# config-ground.net
KiCad netlist of a schematic drawn in Altium Designer
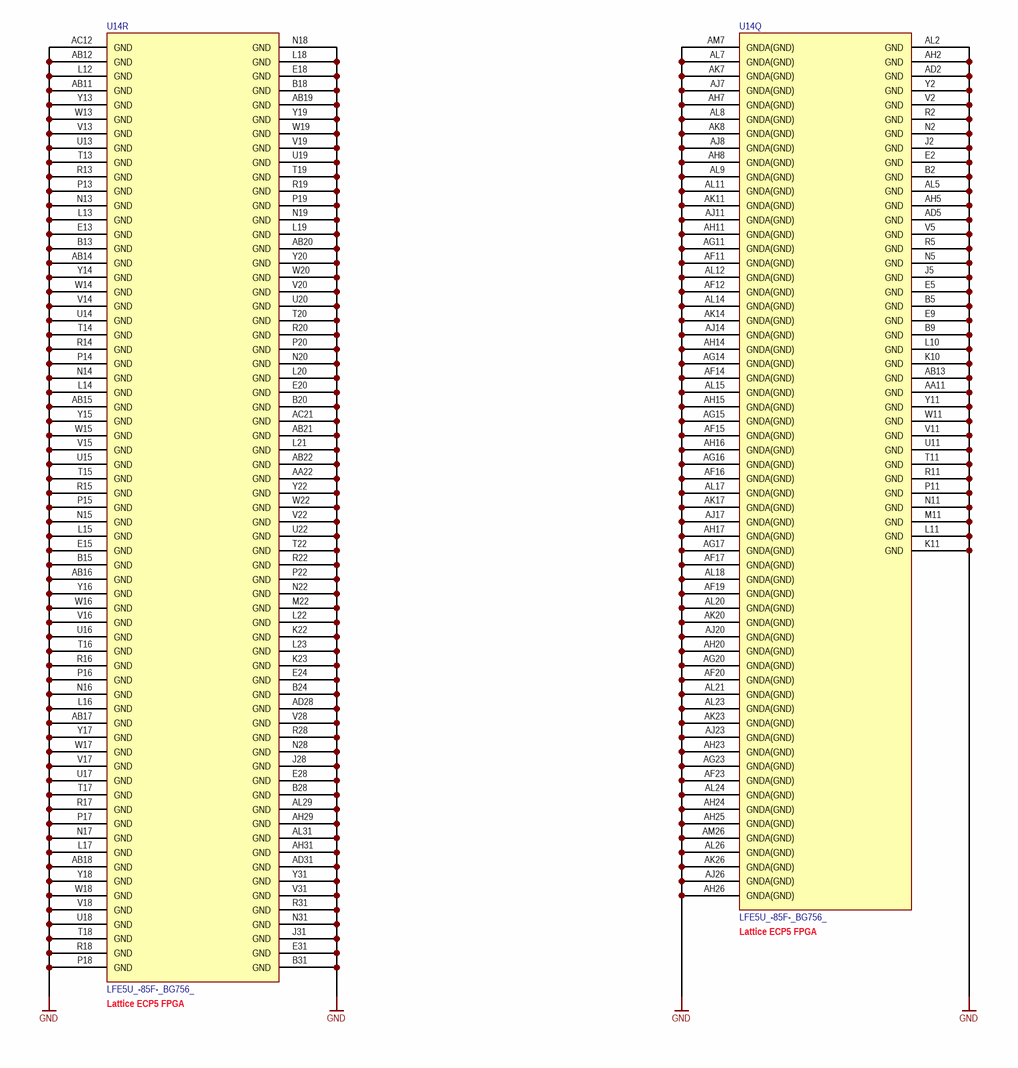
[diagram p0: config-ground.SchDoc]

(export (version "E")
  (design (tool "Eeschema 10.0.6"))
  (components
    (comp (ref "U14")
      (value "LFE5U_-85F-_BG756_")
      (footprint "lattice:caBGA756")
      (description "ECP5 FPGA, 85k LUT, 756-caBGA")
      (fields (field (name "MANUFACTURER") "Lattice Semiconductor"))
      (libsource (lib "lattice") (part "LFE5U_-85F-_BG756_"))
    )
  )
  (nets
    (net (code "1") (name "GND") (class "Default")
      (node (ref "U14") (pin "AA11") (pinfunction "GND_AA11") (pintype "power_in"))
      (node (ref "U14") (pin "AA22") (pinfunction "GND_AA22") (pintype "power_in"))
      (node (ref "U14") (pin "AB11") (pinfunction "GND_AB11") (pintype "power_in"))
      (node (ref "U14") (pin "AB12") (pinfunction "GND_AB12") (pintype "power_in"))
      (node (ref "U14") (pin "AB13") (pinfunction "GND_AB13") (pintype "power_in"))
      (node (ref "U14") (pin "AB14") (pinfunction "GND_AB14") (pintype "power_in"))
      (node (ref "U14") (pin "AB15") (pinfunction "GND_AB15") (pintype "power_in"))
      (node (ref "U14") (pin "AB16") (pinfunction "GND_AB16") (pintype "power_in"))
      (node (ref "U14") (pin "AB17") (pinfunction "GND_AB17") (pintype "power_in"))
      (node (ref "U14") (pin "AB18") (pinfunction "GND_AB18") (pintype "power_in"))
      (node (ref "U14") (pin "AB19") (pinfunction "GND_AB19") (pintype "power_in"))
      (node (ref "U14") (pin "AB20") (pinfunction "GND_AB20") (pintype "power_in"))
      (node (ref "U14") (pin "AB21") (pinfunction "GND_AB21") (pintype "power_in"))
      (node (ref "U14") (pin "AB22") (pinfunction "GND_AB22") (pintype "power_in"))
      (node (ref "U14") (pin "AC12") (pinfunction "GND_AC12") (pintype "power_in"))
      (node (ref "U14") (pin "AC21") (pinfunction "GND_AC21") (pintype "power_in"))
      (node (ref "U14") (pin "AD2") (pinfunction "GND_AD2") (pintype "power_in"))
      (node (ref "U14") (pin "AD28") (pinfunction "GND_AD28") (pintype "power_in"))
      (node (ref "U14") (pin "AD31") (pinfunction "GND_AD31") (pintype "power_in"))
      (node (ref "U14") (pin "AD5") (pinfunction "GND_AD5") (pintype "power_in"))
      (node (ref "U14") (pin "AF11") (pinfunction "GNDA(GND)_AF11") (pintype "power_in"))
      (node (ref "U14") (pin "AF12") (pinfunction "GNDA(GND)_AF12") (pintype "power_in"))
      (node (ref "U14") (pin "AF14") (pinfunction "GNDA(GND)_AF14") (pintype "power_in"))
      (node (ref "U14") (pin "AF15") (pinfunction "GNDA(GND)_AF15") (pintype "power_in"))
      (node (ref "U14") (pin "AF16") (pinfunction "GNDA(GND)_AF16") (pintype "power_in"))
      (node (ref "U14") (pin "AF17") (pinfunction "GNDA(GND)_AF17") (pintype "power_in"))
      (node (ref "U14") (pin "AF19") (pinfunction "GNDA(GND)_AF19") (pintype "power_in"))
      (node (ref "U14") (pin "AF20") (pinfunction "GNDA(GND)_AF20") (pintype "power_in"))
      (node (ref "U14") (pin "AF23") (pinfunction "GNDA(GND)_AF23") (pintype "power_in"))
      (node (ref "U14") (pin "AG11") (pinfunction "GNDA(GND)_AG11") (pintype "power_in"))
      (node (ref "U14") (pin "AG14") (pinfunction "GNDA(GND)_AG14") (pintype "power_in"))
      (node (ref "U14") (pin "AG15") (pinfunction "GNDA(GND)_AG15") (pintype "power_in"))
      (node (ref "U14") (pin "AG16") (pinfunction "GNDA(GND)_AG16") (pintype "power_in"))
      (node (ref "U14") (pin "AG17") (pinfunction "GNDA(GND)_AG17") (pintype "power_in"))
      (node (ref "U14") (pin "AG20") (pinfunction "GNDA(GND)_AG20") (pintype "power_in"))
      (node (ref "U14") (pin "AG23") (pinfunction "GNDA(GND)_AG23") (pintype "power_in"))
      (node (ref "U14") (pin "AH11") (pinfunction "GNDA(GND)_AH11") (pintype "power_in"))
      (node (ref "U14") (pin "AH14") (pinfunction "GNDA(GND)_AH14") (pintype "power_in"))
      (node (ref "U14") (pin "AH15") (pinfunction "GNDA(GND)_AH15") (pintype "power_in"))
      (node (ref "U14") (pin "AH16") (pinfunction "GNDA(GND)_AH16") (pintype "power_in"))
      (node (ref "U14") (pin "AH17") (pinfunction "GNDA(GND)_AH17") (pintype "power_in"))
      (node (ref "U14") (pin "AH2") (pinfunction "GND_AH2") (pintype "power_in"))
      (node (ref "U14") (pin "AH20") (pinfunction "GNDA(GND)_AH20") (pintype "power_in"))
      (node (ref "U14") (pin "AH23") (pinfunction "GNDA(GND)_AH23") (pintype "power_in"))
      (node (ref "U14") (pin "AH24") (pinfunction "GNDA(GND)_AH24") (pintype "power_in"))
      (node (ref "U14") (pin "AH25") (pinfunction "GNDA(GND)_AH25") (pintype "power_in"))
      (node (ref "U14") (pin "AH26") (pinfunction "GNDA(GND)_AH26") (pintype "power_in"))
      (node (ref "U14") (pin "AH29") (pinfunction "GND_AH29") (pintype "power_in"))
      (node (ref "U14") (pin "AH31") (pinfunction "GND_AH31") (pintype "power_in"))
      (node (ref "U14") (pin "AH5") (pinfunction "GND_AH5") (pintype "power_in"))
      (node (ref "U14") (pin "AH7") (pinfunction "GNDA(GND)_AH7") (pintype "power_in"))
      (node (ref "U14") (pin "AH8") (pinfunction "GNDA(GND)_AH8") (pintype "power_in"))
      (node (ref "U14") (pin "AJ11") (pinfunction "GNDA(GND)_AJ11") (pintype "power_in"))
      (node (ref "U14") (pin "AJ14") (pinfunction "GNDA(GND)_AJ14") (pintype "power_in"))
      (node (ref "U14") (pin "AJ17") (pinfunction "GNDA(GND)_AJ17") (pintype "power_in"))
      (node (ref "U14") (pin "AJ20") (pinfunction "GNDA(GND)_AJ20") (pintype "power_in"))
      (node (ref "U14") (pin "AJ23") (pinfunction "GNDA(GND)_AJ23") (pintype "power_in"))
      (node (ref "U14") (pin "AJ26") (pinfunction "GNDA(GND)_AJ26") (pintype "power_in"))
      (node (ref "U14") (pin "AJ7") (pinfunction "GNDA(GND)_AJ7") (pintype "power_in"))
      (node (ref "U14") (pin "AJ8") (pinfunction "GNDA(GND)_AJ8") (pintype "power_in"))
      (node (ref "U14") (pin "AK11") (pinfunction "GNDA(GND)_AK11") (pintype "power_in"))
      (node (ref "U14") (pin "AK14") (pinfunction "GNDA(GND)_AK14") (pintype "power_in"))
      (node (ref "U14") (pin "AK17") (pinfunction "GNDA(GND)_AK17") (pintype "power_in"))
      (node (ref "U14") (pin "AK20") (pinfunction "GNDA(GND)_AK20") (pintype "power_in"))
      (node (ref "U14") (pin "AK23") (pinfunction "GNDA(GND)_AK23") (pintype "power_in"))
      (node (ref "U14") (pin "AK26") (pinfunction "GNDA(GND)_AK26") (pintype "power_in"))
      (node (ref "U14") (pin "AK7") (pinfunction "GNDA(GND)_AK7") (pintype "power_in"))
      (node (ref "U14") (pin "AK8") (pinfunction "GNDA(GND)_AK8") (pintype "power_in"))
      (node (ref "U14") (pin "AL11") (pinfunction "GNDA(GND)_AL11") (pintype "power_in"))
      (node (ref "U14") (pin "AL12") (pinfunction "GNDA(GND)_AL12") (pintype "power_in"))
      (node (ref "U14") (pin "AL14") (pinfunction "GNDA(GND)_AL14") (pintype "power_in"))
      (node (ref "U14") (pin "AL15") (pinfunction "GNDA(GND)_AL15") (pintype "power_in"))
      (node (ref "U14") (pin "AL17") (pinfunction "GNDA(GND)_AL17") (pintype "power_in"))
      (node (ref "U14") (pin "AL18") (pinfunction "GNDA(GND)_AL18") (pintype "power_in"))
      (node (ref "U14") (pin "AL2") (pinfunction "GND_AL2") (pintype "power_in"))
      (node (ref "U14") (pin "AL20") (pinfunction "GNDA(GND)_AL20") (pintype "power_in"))
      (node (ref "U14") (pin "AL21") (pinfunction "GNDA(GND)_AL21") (pintype "power_in"))
      (node (ref "U14") (pin "AL23") (pinfunction "GNDA(GND)_AL23") (pintype "power_in"))
      (node (ref "U14") (pin "AL24") (pinfunction "GNDA(GND)_AL24") (pintype "power_in"))
      (node (ref "U14") (pin "AL26") (pinfunction "GNDA(GND)_AL26") (pintype "power_in"))
      (node (ref "U14") (pin "AL29") (pinfunction "GND_AL29") (pintype "power_in"))
      (node (ref "U14") (pin "AL31") (pinfunction "GND_AL31") (pintype "power_in"))
      (node (ref "U14") (pin "AL5") (pinfunction "GND_AL5") (pintype "power_in"))
      (node (ref "U14") (pin "AL7") (pinfunction "GNDA(GND)_AL7") (pintype "power_in"))
      (node (ref "U14") (pin "AL8") (pinfunction "GNDA(GND)_AL8") (pintype "power_in"))
      (node (ref "U14") (pin "AL9") (pinfunction "GNDA(GND)_AL9") (pintype "power_in"))
      (node (ref "U14") (pin "AM26") (pinfunction "GNDA(GND)_AM26") (pintype "power_in"))
      (node (ref "U14") (pin "AM7") (pinfunction "GNDA(GND)_AM7") (pintype "power_in"))
      (node (ref "U14") (pin "B13") (pinfunction "GND_B13") (pintype "power_in"))
      (node (ref "U14") (pin "B15") (pinfunction "GND_B15") (pintype "power_in"))
      (node (ref "U14") (pin "B18") (pinfunction "GND_B18") (pintype "power_in"))
      (node (ref "U14") (pin "B2") (pinfunction "GND_B2") (pintype "power_in"))
      (node (ref "U14") (pin "B20") (pinfunction "GND_B20") (pintype "power_in"))
      (node (ref "U14") (pin "B24") (pinfunction "GND_B24") (pintype "power_in"))
      (node (ref "U14") (pin "B28") (pinfunction "GND_B28") (pintype "power_in"))
      (node (ref "U14") (pin "B31") (pinfunction "GND_B31") (pintype "power_in"))
      (node (ref "U14") (pin "B5") (pinfunction "GND_B5") (pintype "power_in"))
      (node (ref "U14") (pin "B9") (pinfunction "GND_B9") (pintype "power_in"))
      (node (ref "U14") (pin "E13") (pinfunction "GND_E13") (pintype "power_in"))
      (node (ref "U14") (pin "E15") (pinfunction "GND_E15") (pintype "power_in"))
      (node (ref "U14") (pin "E18") (pinfunction "GND_E18") (pintype "power_in"))
      (node (ref "U14") (pin "E2") (pinfunction "GND_E2") (pintype "power_in"))
      (node (ref "U14") (pin "E20") (pinfunction "GND_E20") (pintype "power_in"))
      (node (ref "U14") (pin "E24") (pinfunction "GND_E24") (pintype "power_in"))
      (node (ref "U14") (pin "E28") (pinfunction "GND_E28") (pintype "power_in"))
      (node (ref "U14") (pin "E31") (pinfunction "GND_E31") (pintype "power_in"))
      (node (ref "U14") (pin "E5") (pinfunction "GND_E5") (pintype "power_in"))
      (node (ref "U14") (pin "E9") (pinfunction "GND_E9") (pintype "power_in"))
      (node (ref "U14") (pin "J2") (pinfunction "GND_J2") (pintype "power_in"))
      (node (ref "U14") (pin "J28") (pinfunction "GND_J28") (pintype "power_in"))
      (node (ref "U14") (pin "J31") (pinfunction "GND_J31") (pintype "power_in"))
      (node (ref "U14") (pin "J5") (pinfunction "GND_J5") (pintype "power_in"))
      (node (ref "U14") (pin "K10") (pinfunction "GND_K10") (pintype "power_in"))
      (node (ref "U14") (pin "K11") (pinfunction "GND_K11") (pintype "power_in"))
      (node (ref "U14") (pin "K22") (pinfunction "GND_K22") (pintype "power_in"))
      (node (ref "U14") (pin "K23") (pinfunction "GND_K23") (pintype "power_in"))
      (node (ref "U14") (pin "L10") (pinfunction "GND_L10") (pintype "power_in"))
      (node (ref "U14") (pin "L11") (pinfunction "GND_L11") (pintype "power_in"))
      (node (ref "U14") (pin "L12") (pinfunction "GND_L12") (pintype "power_in"))
      (node (ref "U14") (pin "L13") (pinfunction "GND_L13") (pintype "power_in"))
      (node (ref "U14") (pin "L14") (pinfunction "GND_L14") (pintype "power_in"))
      (node (ref "U14") (pin "L15") (pinfunction "GND_L15") (pintype "power_in"))
      (node (ref "U14") (pin "L16") (pinfunction "GND_L16") (pintype "power_in"))
      (node (ref "U14") (pin "L17") (pinfunction "GND_L17") (pintype "power_in"))
      (node (ref "U14") (pin "L18") (pinfunction "GND_L18") (pintype "power_in"))
      (node (ref "U14") (pin "L19") (pinfunction "GND_L19") (pintype "power_in"))
      (node (ref "U14") (pin "L20") (pinfunction "GND_L20") (pintype "power_in"))
      (node (ref "U14") (pin "L21") (pinfunction "GND_L21") (pintype "power_in"))
      (node (ref "U14") (pin "L22") (pinfunction "GND_L22") (pintype "power_in"))
      (node (ref "U14") (pin "L23") (pinfunction "GND_L23") (pintype "power_in"))
      (node (ref "U14") (pin "M11") (pinfunction "GND_M11") (pintype "power_in"))
      (node (ref "U14") (pin "M22") (pinfunction "GND_M22") (pintype "power_in"))
      (node (ref "U14") (pin "N11") (pinfunction "GND_N11") (pintype "power_in"))
      (node (ref "U14") (pin "N13") (pinfunction "GND_N13") (pintype "power_in"))
      (node (ref "U14") (pin "N14") (pinfunction "GND_N14") (pintype "power_in"))
      (node (ref "U14") (pin "N15") (pinfunction "GND_N15") (pintype "power_in"))
      (node (ref "U14") (pin "N16") (pinfunction "GND_N16") (pintype "power_in"))
      (node (ref "U14") (pin "N17") (pinfunction "GND_N17") (pintype "power_in"))
      (node (ref "U14") (pin "N18") (pinfunction "GND_N18") (pintype "power_in"))
      (node (ref "U14") (pin "N19") (pinfunction "GND_N19") (pintype "power_in"))
      (node (ref "U14") (pin "N2") (pinfunction "GND_N2") (pintype "power_in"))
      (node (ref "U14") (pin "N20") (pinfunction "GND_N20") (pintype "power_in"))
      (node (ref "U14") (pin "N22") (pinfunction "GND_N22") (pintype "power_in"))
      (node (ref "U14") (pin "N28") (pinfunction "GND_N28") (pintype "power_in"))
      (node (ref "U14") (pin "N31") (pinfunction "GND_N31") (pintype "power_in"))
      (node (ref "U14") (pin "N5") (pinfunction "GND_N5") (pintype "power_in"))
      (node (ref "U14") (pin "P11") (pinfunction "GND_P11") (pintype "power_in"))
      (node (ref "U14") (pin "P13") (pinfunction "GND_P13") (pintype "power_in"))
      (node (ref "U14") (pin "P14") (pinfunction "GND_P14") (pintype "power_in"))
      (node (ref "U14") (pin "P15") (pinfunction "GND_P15") (pintype "power_in"))
      (node (ref "U14") (pin "P16") (pinfunction "GND_P16") (pintype "power_in"))
      (node (ref "U14") (pin "P17") (pinfunction "GND_P17") (pintype "power_in"))
      (node (ref "U14") (pin "P18") (pinfunction "GND_P18") (pintype "power_in"))
      (node (ref "U14") (pin "P19") (pinfunction "GND_P19") (pintype "power_in"))
      (node (ref "U14") (pin "P20") (pinfunction "GND_P20") (pintype "power_in"))
      (node (ref "U14") (pin "P22") (pinfunction "GND_P22") (pintype "power_in"))
      (node (ref "U14") (pin "R11") (pinfunction "GND_R11") (pintype "power_in"))
      (node (ref "U14") (pin "R13") (pinfunction "GND_R13") (pintype "power_in"))
      (node (ref "U14") (pin "R14") (pinfunction "GND_R14") (pintype "power_in"))
      (node (ref "U14") (pin "R15") (pinfunction "GND_R15") (pintype "power_in"))
      (node (ref "U14") (pin "R16") (pinfunction "GND_R16") (pintype "power_in"))
      (node (ref "U14") (pin "R17") (pinfunction "GND_R17") (pintype "power_in"))
      (node (ref "U14") (pin "R18") (pinfunction "GND_R18") (pintype "power_in"))
      (node (ref "U14") (pin "R19") (pinfunction "GND_R19") (pintype "power_in"))
      (node (ref "U14") (pin "R2") (pinfunction "GND_R2") (pintype "power_in"))
      (node (ref "U14") (pin "R20") (pinfunction "GND_R20") (pintype "power_in"))
      (node (ref "U14") (pin "R22") (pinfunction "GND_R22") (pintype "power_in"))
      (node (ref "U14") (pin "R28") (pinfunction "GND_R28") (pintype "power_in"))
      (node (ref "U14") (pin "R31") (pinfunction "GND_R31") (pintype "power_in"))
      (node (ref "U14") (pin "R5") (pinfunction "GND_R5") (pintype "power_in"))
      (node (ref "U14") (pin "T11") (pinfunction "GND_T11") (pintype "power_in"))
      (node (ref "U14") (pin "T13") (pinfunction "GND_T13") (pintype "power_in"))
      (node (ref "U14") (pin "T14") (pinfunction "GND_T14") (pintype "power_in"))
      (node (ref "U14") (pin "T15") (pinfunction "GND_T15") (pintype "power_in"))
      (node (ref "U14") (pin "T16") (pinfunction "GND_T16") (pintype "power_in"))
      (node (ref "U14") (pin "T17") (pinfunction "GND_T17") (pintype "power_in"))
      (node (ref "U14") (pin "T18") (pinfunction "GND_T18") (pintype "power_in"))
      (node (ref "U14") (pin "T19") (pinfunction "GND_T19") (pintype "power_in"))
      (node (ref "U14") (pin "T20") (pinfunction "GND_T20") (pintype "power_in"))
      (node (ref "U14") (pin "T22") (pinfunction "GND_T22") (pintype "power_in"))
      (node (ref "U14") (pin "U11") (pinfunction "GND_U11") (pintype "power_in"))
      (node (ref "U14") (pin "U13") (pinfunction "GND_U13") (pintype "power_in"))
      (node (ref "U14") (pin "U14") (pinfunction "GND_U14") (pintype "power_in"))
      (node (ref "U14") (pin "U15") (pinfunction "GND_U15") (pintype "power_in"))
      (node (ref "U14") (pin "U16") (pinfunction "GND_U16") (pintype "power_in"))
      (node (ref "U14") (pin "U17") (pinfunction "GND_U17") (pintype "power_in"))
      (node (ref "U14") (pin "U18") (pinfunction "GND_U18") (pintype "power_in"))
      (node (ref "U14") (pin "U19") (pinfunction "GND_U19") (pintype "power_in"))
      (node (ref "U14") (pin "U20") (pinfunction "GND_U20") (pintype "power_in"))
      (node (ref "U14") (pin "U22") (pinfunction "GND_U22") (pintype "power_in"))
      (node (ref "U14") (pin "V11") (pinfunction "GND_V11") (pintype "power_in"))
      (node (ref "U14") (pin "V13") (pinfunction "GND_V13") (pintype "power_in"))
      (node (ref "U14") (pin "V14") (pinfunction "GND_V14") (pintype "power_in"))
      (node (ref "U14") (pin "V15") (pinfunction "GND_V15") (pintype "power_in"))
      (node (ref "U14") (pin "V16") (pinfunction "GND_V16") (pintype "power_in"))
      (node (ref "U14") (pin "V17") (pinfunction "GND_V17") (pintype "power_in"))
      (node (ref "U14") (pin "V18") (pinfunction "GND_V18") (pintype "power_in"))
      (node (ref "U14") (pin "V19") (pinfunction "GND_V19") (pintype "power_in"))
      (node (ref "U14") (pin "V2") (pinfunction "GND_V2") (pintype "power_in"))
      (node (ref "U14") (pin "V20") (pinfunction "GND_V20") (pintype "power_in"))
      (node (ref "U14") (pin "V22") (pinfunction "GND_V22") (pintype "power_in"))
      (node (ref "U14") (pin "V28") (pinfunction "GND_V28") (pintype "power_in"))
      (node (ref "U14") (pin "V31") (pinfunction "GND_V31") (pintype "power_in"))
      (node (ref "U14") (pin "V5") (pinfunction "GND_V5") (pintype "power_in"))
      (node (ref "U14") (pin "W11") (pinfunction "GND_W11") (pintype "power_in"))
      (node (ref "U14") (pin "W13") (pinfunction "GND_W13") (pintype "power_in"))
      (node (ref "U14") (pin "W14") (pinfunction "GND_W14") (pintype "power_in"))
      (node (ref "U14") (pin "W15") (pinfunction "GND_W15") (pintype "power_in"))
      (node (ref "U14") (pin "W16") (pinfunction "GND_W16") (pintype "power_in"))
      (node (ref "U14") (pin "W17") (pinfunction "GND_W17") (pintype "power_in"))
      (node (ref "U14") (pin "W18") (pinfunction "GND_W18") (pintype "power_in"))
      (node (ref "U14") (pin "W19") (pinfunction "GND_W19") (pintype "power_in"))
      (node (ref "U14") (pin "W20") (pinfunction "GND_W20") (pintype "power_in"))
      (node (ref "U14") (pin "W22") (pinfunction "GND_W22") (pintype "power_in"))
      (node (ref "U14") (pin "Y11") (pinfunction "GND_Y11") (pintype "power_in"))
      (node (ref "U14") (pin "Y13") (pinfunction "GND_Y13") (pintype "power_in"))
      (node (ref "U14") (pin "Y14") (pinfunction "GND_Y14") (pintype "power_in"))
      (node (ref "U14") (pin "Y15") (pinfunction "GND_Y15") (pintype "power_in"))
      (node (ref "U14") (pin "Y16") (pinfunction "GND_Y16") (pintype "power_in"))
      (node (ref "U14") (pin "Y17") (pinfunction "GND_Y17") (pintype "power_in"))
      (node (ref "U14") (pin "Y18") (pinfunction "GND_Y18") (pintype "power_in"))
      (node (ref "U14") (pin "Y19") (pinfunction "GND_Y19") (pintype "power_in"))
      (node (ref "U14") (pin "Y2") (pinfunction "GND_Y2") (pintype "power_in"))
      (node (ref "U14") (pin "Y20") (pinfunction "GND_Y20") (pintype "power_in"))
      (node (ref "U14") (pin "Y22") (pinfunction "GND_Y22") (pintype "power_in"))
      (node (ref "U14") (pin "Y31") (pinfunction "GND_Y31") (pintype "power_in"))
    )
  )
)
